# LB_BIT_w8-latch_v03_1_1.net
KiCad netlist of a schematic drawn in EAGLE
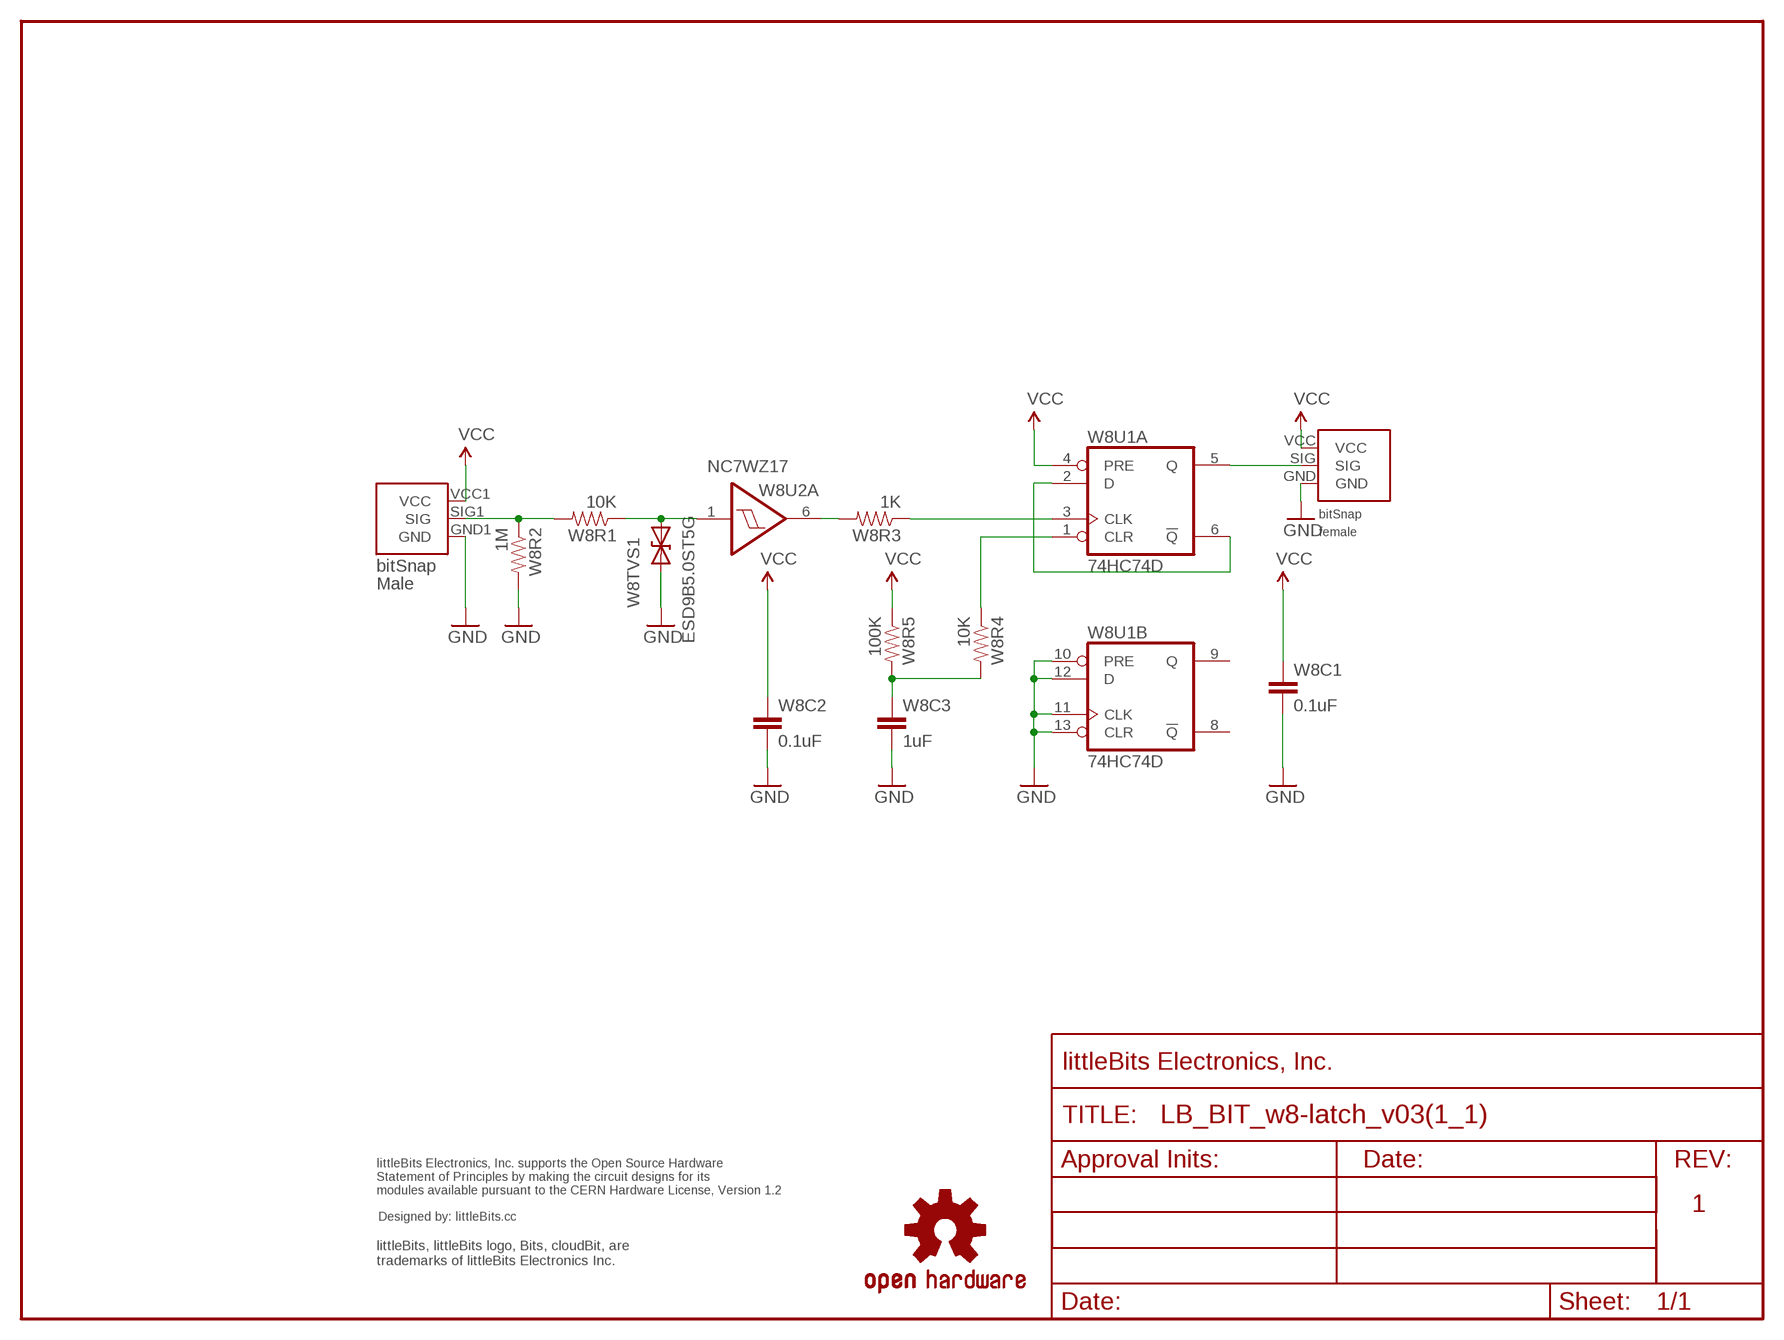
[diagram p0: schematic, sheet 1]

(export (version "E")
  (design (tool "Eeschema 10.0.6"))
  (components
    (comp (ref "U$1")
      (value "OSHW-LOGOL")
      (footprint "eagle-import:OSHW-LOGO-L")
      (libsource (lib "eagle-import") (part "OSHW-LOGOL"))
    )
    (comp (ref "U$2")
      (value "OSHWCREDIT")
      (footprint "eagle-import:OSHWCREDIT")
      (libsource (lib "eagle-import") (part "OSHWCREDIT"))
    )
    (comp (ref "U$12")
      (value "FRAME-LETTER-OHWOHW")
      (footprint "eagle-import:FABDWG01-OHW")
      (libsource (lib "eagle-import") (part "FRAME-LETTER-OHWOHW"))
    )
    (comp (ref "W8BSF1")
      (value "BITSNAP_V03_FEMALE")
      (footprint "eagle-import:BITSNAP_V03_FEMALE")
      (libsource (lib "eagle-import") (part "BITSNAP_V03_FEMALE"))
    )
    (comp (ref "W8BSM1")
      (value "BITSNAP_V03_MALE")
      (footprint "eagle-import:BITSNAP_V03_MALE")
      (libsource (lib "eagle-import") (part "BITSNAP_V03_MALE"))
    )
    (comp (ref "W8C1")
      (value "0.1uF")
      (footprint "eagle-import:0603-CAP")
      (libsource (lib "eagle-import") (part "CAP0603-CAP"))
    )
    (comp (ref "W8C2")
      (value "0.1uF")
      (footprint "eagle-import:0603-CAP")
      (libsource (lib "eagle-import") (part "CAP0603-CAP"))
    )
    (comp (ref "W8C3")
      (value "1uF")
      (footprint "eagle-import:0603-CAP")
      (libsource (lib "eagle-import") (part "CAP0603-CAP"))
    )
    (comp (ref "W8R1")
      (value "10K")
      (footprint "eagle-import:0603-RES")
      (libsource (lib "eagle-import") (part "RESISTOR0603-RES"))
    )
    (comp (ref "W8R2")
      (value "1M")
      (footprint "eagle-import:0603-RES")
      (libsource (lib "eagle-import") (part "RESISTOR0603-RES"))
    )
    (comp (ref "W8R3")
      (value "1K")
      (footprint "eagle-import:0603-RES")
      (libsource (lib "eagle-import") (part "RESISTOR0603-RES"))
    )
    (comp (ref "W8R4")
      (value "10K")
      (footprint "eagle-import:0603-RES")
      (libsource (lib "eagle-import") (part "RESISTOR0603-RES"))
    )
    (comp (ref "W8R5")
      (value "100K")
      (footprint "eagle-import:0603-RES")
      (libsource (lib "eagle-import") (part "RESISTOR0603-RES"))
    )
    (comp (ref "W8TVS1")
      (value "ESD9B5.0ST5G")
      (footprint "eagle-import:SOD-923")
      (libsource (lib "eagle-import") (part "DIODE-TVSSOD-923"))
    )
    (comp (ref "W8U1")
      (value "74HC74D")
      (footprint "eagle-import:SO14")
      (libsource (lib "eagle-import") (part "7474DHC"))
    )
    (comp (ref "W8U2")
      (value "SCHMITT_TRIGGER_NON_INVERTINGNC7WZ17")
      (footprint "eagle-import:SC70-6")
      (libsource (lib "eagle-import") (part "SCHMITT_TRIGGER_NON_INVERTINGNC7WZ17"))
    )
  )
  (nets
    (net (code "1") (name "GND") (class "Default")
      (node (ref "W8BSF1") (pin "GND") (pinfunction "GND_GND") (pintype "bidirectional"))
      (node (ref "W8BSM1") (pin "GND1") (pinfunction "GND_GND1") (pintype "bidirectional"))
      (node (ref "W8C1") (pin "2") (pinfunction "2_2") (pintype "passive"))
      (node (ref "W8C2") (pin "2") (pinfunction "2_2") (pintype "passive"))
      (node (ref "W8C3") (pin "2") (pinfunction "2_2") (pintype "passive"))
      (node (ref "W8R2") (pin "2") (pinfunction "2_2") (pintype "passive"))
      (node (ref "W8TVS1") (pin "1") (pinfunction "A_1") (pintype "passive"))
      (node (ref "W8U1") (pin "10") (pinfunction "PRE_10") (pintype "input"))
      (node (ref "W8U1") (pin "11") (pinfunction "CLK_11") (pintype "input"))
      (node (ref "W8U1") (pin "12") (pinfunction "D_12") (pintype "input"))
      (node (ref "W8U1") (pin "13") (pinfunction "CLR_13") (pintype "input"))
    )
    (net (code "2") (name "Net-(W8BSM1-SIG)") (class "Default")
      (node (ref "W8BSM1") (pin "SIG1") (pinfunction "SIG_SIG1") (pintype "bidirectional"))
      (node (ref "W8R1") (pin "2") (pinfunction "2_2") (pintype "passive"))
      (node (ref "W8R2") (pin "1") (pinfunction "1_1") (pintype "passive"))
    )
    (net (code "3") (name "Net-(W8C3-Pad1)") (class "Default")
      (node (ref "W8C3") (pin "1") (pinfunction "1_1") (pintype "passive"))
      (node (ref "W8R4") (pin "2") (pinfunction "2_2") (pintype "passive"))
      (node (ref "W8R5") (pin "2") (pinfunction "2_2") (pintype "passive"))
    )
    (net (code "4") (name "Net-(W8TVS1-C)") (class "Default")
      (node (ref "W8R1") (pin "1") (pinfunction "1_1") (pintype "passive"))
      (node (ref "W8TVS1") (pin "2") (pinfunction "C_2") (pintype "passive"))
      (node (ref "W8U2") (pin "1") (pinfunction "I_1") (pintype "input"))
    )
    (net (code "5") (name "Net-(W8U1A-CLK)") (class "Default")
      (node (ref "W8R3") (pin "1") (pinfunction "1_1") (pintype "passive"))
      (node (ref "W8U1") (pin "3") (pinfunction "CLK_3") (pintype "input"))
    )
    (net (code "6") (name "Net-(W8U1A-CLR)") (class "Default")
      (node (ref "W8R4") (pin "1") (pinfunction "1_1") (pintype "passive"))
      (node (ref "W8U1") (pin "1") (pinfunction "CLR_1") (pintype "input"))
    )
    (net (code "7") (name "Net-(W8U1A-D)") (class "Default")
      (node (ref "W8U1") (pin "2") (pinfunction "D_2") (pintype "input"))
      (node (ref "W8U1") (pin "6") (pinfunction "~{Q}_6") (pintype "output"))
    )
    (net (code "8") (name "Net-(W8U1A-Q)") (class "Default")
      (node (ref "W8BSF1") (pin "SIG") (pinfunction "SIG_SIG") (pintype "bidirectional"))
      (node (ref "W8U1") (pin "5") (pinfunction "Q_5") (pintype "output"))
    )
    (net (code "9") (name "Net-(W8U2A-O)") (class "Default")
      (node (ref "W8R3") (pin "2") (pinfunction "2_2") (pintype "passive"))
      (node (ref "W8U2") (pin "6") (pinfunction "O_6") (pintype "output"))
    )
    (net (code "10") (name "VCC") (class "Default")
      (node (ref "W8BSF1") (pin "VCC") (pinfunction "VCC_VCC") (pintype "bidirectional"))
      (node (ref "W8BSM1") (pin "VCC1") (pinfunction "VCC_VCC1") (pintype "bidirectional"))
      (node (ref "W8C1") (pin "1") (pinfunction "1_1") (pintype "passive"))
      (node (ref "W8C2") (pin "1") (pinfunction "1_1") (pintype "passive"))
      (node (ref "W8R5") (pin "1") (pinfunction "1_1") (pintype "passive"))
      (node (ref "W8U1") (pin "4") (pinfunction "PRE_4") (pintype "input"))
    )
    (net (code "11") (name "unconnected-(W8U1B-Q-Pad9)") (class "Default")
      (node (ref "W8U1") (pin "9") (pinfunction "Q_9") (pintype "output"))
    )
    (net (code "12") (name "unconnected-(W8U1B-~{Q}-Pad8)") (class "Default")
      (node (ref "W8U1") (pin "8") (pinfunction "~{Q}_8") (pintype "output"))
    )
  )
)
